# TDC.net
KiCad netlist of a schematic drawn in Altium Designer
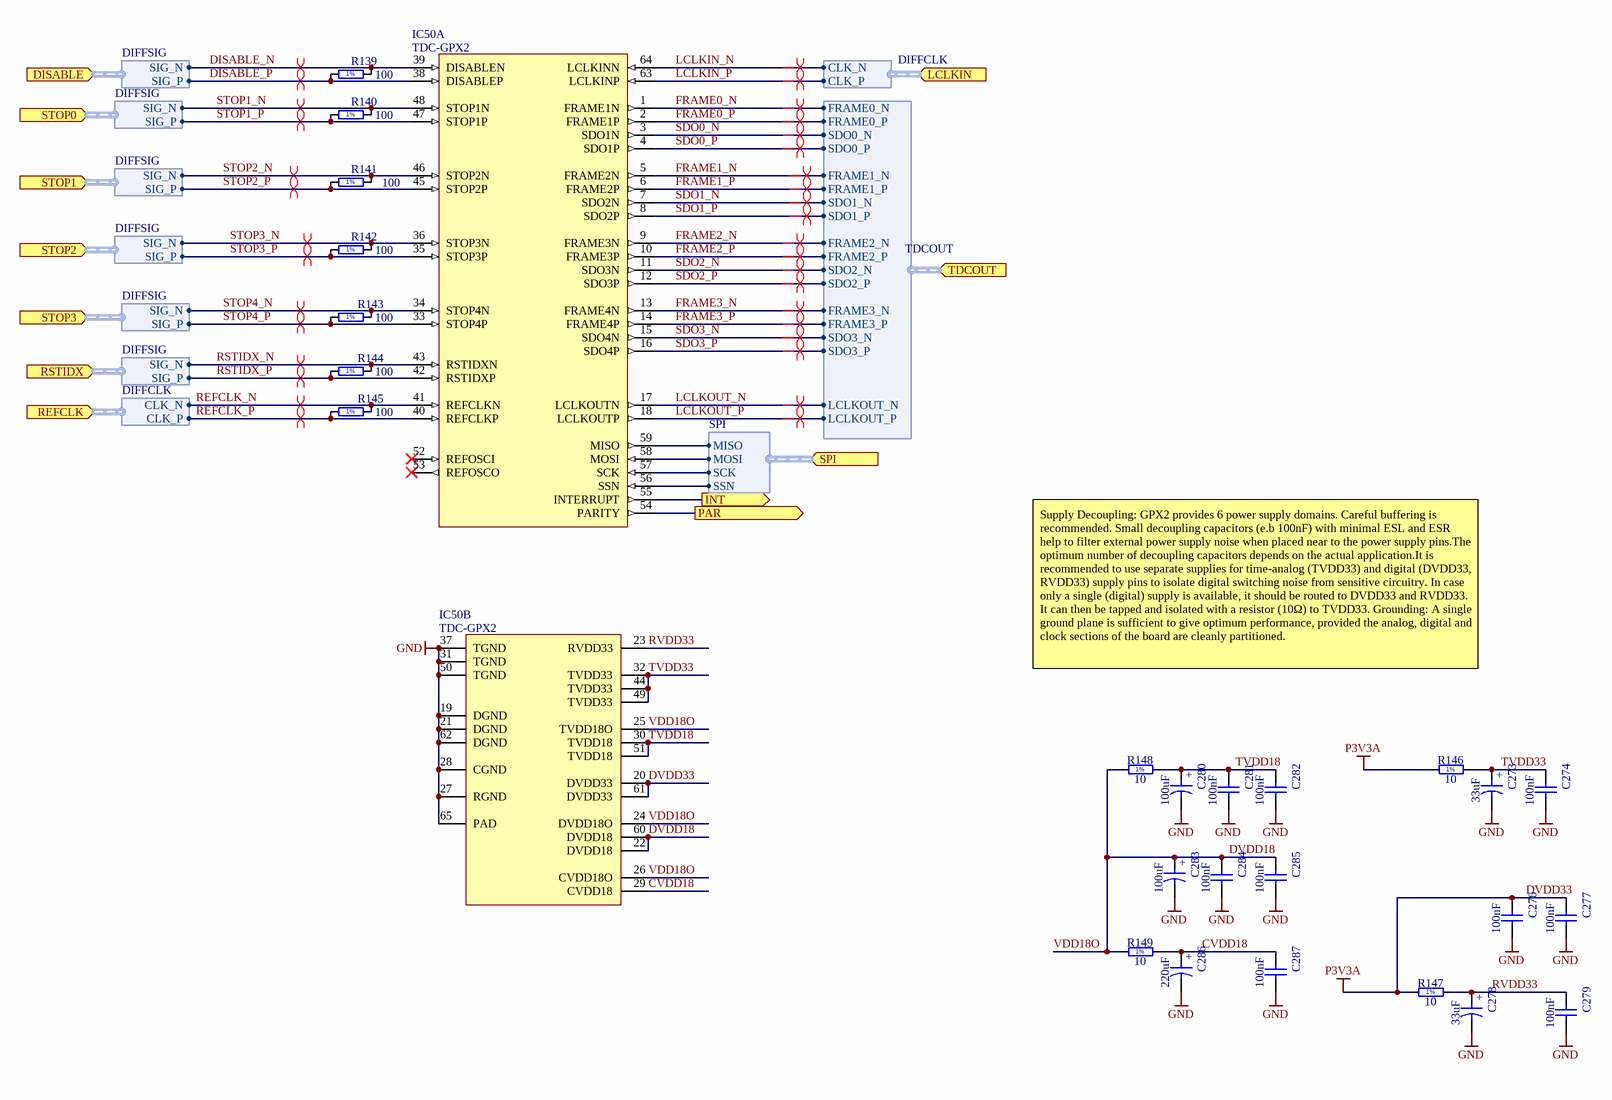
[diagram p0: TDC.SchDoc]

(export (version "E")
  (design (tool "Eeschema 10.0.6"))
  (components
    (comp (ref "C273")
      (value "33uF")
      (footprint "CAPMP3216X180N")
      (description "Polarised capacitor")
      (fields
        (field (name "PART NUMBER") "CTE3216-18_33UF_4V_10%")
        (field (name "VOLTAGE") "4V")
        (field (name "AUTHOR") "CERN DEM JLC")
      )
      (libsource (lib "Capacitors") (part "Capacitor - polarized"))
    )
    (comp (ref "C274")
      (value "100nF")
      (footprint "CAPC0603X33N")
      (description "Non-polarised capacitor")
      (fields
        (field (name "PART NUMBER") "CC0201_100NF_6.3V_10%_X5R")
        (field (name "VOLTAGE") "6.3V")
        (field (name "AUTHOR") "CERN DEM JLC")
      )
      (libsource (lib "Capacitors") (part "Capacitor - non polarized"))
    )
    (comp (ref "C276")
      (value "100nF")
      (footprint "CAPC0603X33N")
      (description "Non-polarised capacitor")
      (fields
        (field (name "PART NUMBER") "CC0201_100NF_6.3V_10%_X5R")
        (field (name "VOLTAGE") "6.3V")
        (field (name "AUTHOR") "CERN DEM JLC")
      )
      (libsource (lib "Capacitors") (part "Capacitor - non polarized"))
    )
    (comp (ref "C277")
      (value "100nF")
      (footprint "CAPC0603X33N")
      (description "Non-polarised capacitor")
      (fields
        (field (name "PART NUMBER") "CC0201_100NF_6.3V_10%_X5R")
        (field (name "VOLTAGE") "6.3V")
        (field (name "AUTHOR") "CERN DEM JLC")
      )
      (libsource (lib "Capacitors") (part "Capacitor - non polarized"))
    )
    (comp (ref "C278")
      (value "33uF")
      (footprint "CAPMP3216X180N")
      (description "Polarised capacitor")
      (fields
        (field (name "PART NUMBER") "CTE3216-18_33UF_4V_10%")
        (field (name "VOLTAGE") "4V")
        (field (name "AUTHOR") "CERN DEM JLC")
      )
      (libsource (lib "Capacitors") (part "Capacitor - polarized"))
    )
    (comp (ref "C279")
      (value "100nF")
      (footprint "CAPC0603X33N")
      (description "Non-polarised capacitor")
      (fields
        (field (name "PART NUMBER") "CC0201_100NF_6.3V_10%_X5R")
        (field (name "VOLTAGE") "6.3V")
        (field (name "AUTHOR") "CERN DEM JLC")
      )
      (libsource (lib "Capacitors") (part "Capacitor - non polarized"))
    )
    (comp (ref "C280")
      (value "100uF")
      (footprint "CAPMP3216X180N")
      (description "Polarised capacitor")
      (fields
        (field (name "PART NUMBER") "CTE3216-18_100UF_6.3V_20%_ESR0500_AVX_TLJ")
        (field (name "VOLTAGE") "6.3V")
        (field (name "AUTHOR") "CERN DEM JLC")
      )
      (libsource (lib "Capacitors") (part "Capacitor - polarized"))
    )
    (comp (ref "C281")
      (value "100nF")
      (footprint "CAPC0603X33N")
      (description "Non-polarised capacitor")
      (fields
        (field (name "PART NUMBER") "CC0201_100NF_6.3V_10%_X5R")
        (field (name "VOLTAGE") "6.3V")
        (field (name "AUTHOR") "CERN DEM JLC")
      )
      (libsource (lib "Capacitors") (part "Capacitor - non polarized"))
    )
    (comp (ref "C282")
      (value "100nF")
      (footprint "CAPC0603X33N")
      (description "Non-polarised capacitor")
      (fields
        (field (name "PART NUMBER") "CC0201_100NF_6.3V_10%_X5R")
        (field (name "VOLTAGE") "6.3V")
        (field (name "AUTHOR") "CERN DEM JLC")
      )
      (libsource (lib "Capacitors") (part "Capacitor - non polarized"))
    )
    (comp (ref "C283")
      (value "100uF")
      (footprint "CAPMP3216X180N")
      (description "Polarised capacitor")
      (fields
        (field (name "PART NUMBER") "CTE3216-18_100UF_6.3V_20%_ESR0500_AVX_TLJ")
        (field (name "VOLTAGE") "6.3V")
        (field (name "AUTHOR") "CERN DEM JLC")
      )
      (libsource (lib "Capacitors") (part "Capacitor - polarized"))
    )
    (comp (ref "C284")
      (value "100nF")
      (footprint "CAPC0603X33N")
      (description "Non-polarised capacitor")
      (fields
        (field (name "PART NUMBER") "CC0201_100NF_6.3V_10%_X5R")
        (field (name "VOLTAGE") "6.3V")
        (field (name "AUTHOR") "CERN DEM JLC")
      )
      (libsource (lib "Capacitors") (part "Capacitor - non polarized"))
    )
    (comp (ref "C285")
      (value "100nF")
      (footprint "CAPC0603X33N")
      (description "Non-polarised capacitor")
      (fields
        (field (name "PART NUMBER") "CC0201_100NF_6.3V_10%_X5R")
        (field (name "VOLTAGE") "6.3V")
        (field (name "AUTHOR") "CERN DEM JLC")
      )
      (libsource (lib "Capacitors") (part "Capacitor - non polarized"))
    )
    (comp (ref "C286")
      (value "220uF")
      (footprint "CAPMP3528X210N")
      (description "Polarised capacitor")
      (fields
        (field (name "PART NUMBER") "CTE3528-21_220UF_2.5V_10%")
        (field (name "VOLTAGE") "2.5V")
        (field (name "AUTHOR") "CERN DEM JLC")
      )
      (libsource (lib "Capacitors") (part "Capacitor - polarized"))
    )
    (comp (ref "C287")
      (value "100nF")
      (footprint "CAPC0603X33N")
      (description "Non-polarised capacitor")
      (fields
        (field (name "PART NUMBER") "CC0201_100NF_6.3V_10%_X5R")
        (field (name "VOLTAGE") "6.3V")
        (field (name "AUTHOR") "CERN DEM JLC")
      )
      (libsource (lib "Capacitors") (part "Capacitor - non polarized"))
    )
    (comp (ref "IC50")
      (value "TDC-GPX2")
      (footprint "QFN50P900X900X100-65N-S615")
      (description "4-Channel Time-to-Digital Converter")
      (fields (field (name "MANUFACTURER") "ACAM MESS-ELECTRONIC") (field (name "AUTHOR") "GK"))
      (libsource (lib "ICs_Analog_Interfaces") (part "TDC-GPX2"))
    )
    (comp (ref "R139")
      (value "100")
      (footprint "RESC0603X28N")
      (description "Resistor - 1%")
      (fields
        (field (name "PART NUMBER") "R0201_100R_1%_0.05W_200PPM")
        (field (name "POWER") "0.05W")
        (field (name "AUTHOR") "CERN DEM JLC")
      )
      (libsource (lib "Resistors") (part "Resistor - 1%"))
    )
    (comp (ref "R140")
      (value "100")
      (footprint "RESC0603X28N")
      (description "Resistor - 1%")
      (fields
        (field (name "PART NUMBER") "R0201_100R_1%_0.05W_200PPM")
        (field (name "POWER") "0.05W")
        (field (name "AUTHOR") "CERN DEM JLC")
      )
      (libsource (lib "Resistors") (part "Resistor - 1%"))
    )
    (comp (ref "R141")
      (value "100")
      (footprint "RESC0603X28N")
      (description "Resistor - 1%")
      (fields
        (field (name "PART NUMBER") "R0201_100R_1%_0.05W_200PPM")
        (field (name "POWER") "0.05W")
        (field (name "AUTHOR") "CERN DEM JLC")
      )
      (libsource (lib "Resistors") (part "Resistor - 1%"))
    )
    (comp (ref "R142")
      (value "100")
      (footprint "RESC0603X28N")
      (description "Resistor - 1%")
      (fields
        (field (name "PART NUMBER") "R0201_100R_1%_0.05W_200PPM")
        (field (name "POWER") "0.05W")
        (field (name "AUTHOR") "CERN DEM JLC")
      )
      (libsource (lib "Resistors") (part "Resistor - 1%"))
    )
    (comp (ref "R143")
      (value "100")
      (footprint "RESC0603X28N")
      (description "Resistor - 1%")
      (fields
        (field (name "PART NUMBER") "R0201_100R_1%_0.05W_200PPM")
        (field (name "POWER") "0.05W")
        (field (name "AUTHOR") "CERN DEM JLC")
      )
      (libsource (lib "Resistors") (part "Resistor - 1%"))
    )
    (comp (ref "R144")
      (value "100")
      (footprint "RESC0603X28N")
      (description "Resistor - 1%")
      (fields
        (field (name "PART NUMBER") "R0201_100R_1%_0.05W_200PPM")
        (field (name "POWER") "0.05W")
        (field (name "AUTHOR") "CERN DEM JLC")
      )
      (libsource (lib "Resistors") (part "Resistor - 1%"))
    )
    (comp (ref "R145")
      (value "100")
      (footprint "RESC0603X28N")
      (description "Resistor - 1%")
      (fields
        (field (name "PART NUMBER") "R0201_100R_1%_0.05W_200PPM")
        (field (name "POWER") "0.05W")
        (field (name "AUTHOR") "CERN DEM JLC")
      )
      (libsource (lib "Resistors") (part "Resistor - 1%"))
    )
    (comp (ref "R146")
      (value "10")
      (footprint "RESC1005X40N")
      (description "Resistor - 1%")
      (fields
        (field (name "PART NUMBER") "R0402_10R_1%_0.0625W_200PPM")
        (field (name "POWER") "0.0625W")
        (field (name "AUTHOR") "CERN DEM JLC")
      )
      (libsource (lib "Resistors") (part "Resistor - 1%"))
    )
    (comp (ref "R147")
      (value "10")
      (footprint "RESC1005X40N")
      (description "Resistor - 1%")
      (fields
        (field (name "PART NUMBER") "R0402_10R_1%_0.0625W_200PPM")
        (field (name "POWER") "0.0625W")
        (field (name "AUTHOR") "CERN DEM JLC")
      )
      (libsource (lib "Resistors") (part "Resistor - 1%"))
    )
    (comp (ref "R148")
      (value "10")
      (footprint "RESC1005X40N")
      (description "Resistor - 1%")
      (fields
        (field (name "PART NUMBER") "R0402_10R_1%_0.0625W_200PPM")
        (field (name "POWER") "0.0625W")
        (field (name "AUTHOR") "CERN DEM JLC")
      )
      (libsource (lib "Resistors") (part "Resistor - 1%"))
    )
    (comp (ref "R149")
      (value "10")
      (footprint "RESC1005X40N")
      (description "Resistor - 1%")
      (fields
        (field (name "PART NUMBER") "R0402_10R_1%_0.0625W_200PPM")
        (field (name "POWER") "0.0625W")
        (field (name "AUTHOR") "CERN DEM JLC")
      )
      (libsource (lib "Resistors") (part "Resistor - 1%"))
    )
  )
  (nets
    (net (code "5") (name "/CVDD18") (class "Default")
      (node (ref "C286") (pin "1") (pinfunction "1_1") (pintype "passive"))
      (node (ref "C287") (pin "1") (pinfunction "1_1") (pintype "passive"))
      (node (ref "IC50") (pin "29") (pinfunction "CVDD18_29") (pintype "power_in"))
      (node (ref "R149") (pin "2") (pinfunction "2_2") (pintype "passive"))
    )
    (net (code "6") (name "/DISABLE_N") (class "Default")
      (node (ref "IC50") (pin "39") (pinfunction "DISABLEN_39") (pintype "input"))
      (node (ref "R139") (pin "2") (pinfunction "2_2") (pintype "passive"))
    )
    (net (code "7") (name "/DISABLE_P") (class "Default")
      (node (ref "IC50") (pin "38") (pinfunction "DISABLEP_38") (pintype "input"))
      (node (ref "R139") (pin "1") (pinfunction "1_1") (pintype "passive"))
    )
    (net (code "8") (name "/DVDD18") (class "Default")
      (node (ref "C283") (pin "1") (pinfunction "1_1") (pintype "passive"))
      (node (ref "C284") (pin "1") (pinfunction "1_1") (pintype "passive"))
      (node (ref "C285") (pin "1") (pinfunction "1_1") (pintype "passive"))
      (node (ref "IC50") (pin "22") (pinfunction "DVDD18_22") (pintype "power_in"))
      (node (ref "IC50") (pin "24") (pinfunction "DVDD18O_24") (pintype "power_in"))
      (node (ref "IC50") (pin "25") (pinfunction "TVDD18O_25") (pintype "power_in"))
      (node (ref "IC50") (pin "26") (pinfunction "CVDD18O_26") (pintype "power_in"))
      (node (ref "IC50") (pin "60") (pinfunction "DVDD18_60") (pintype "power_in"))
      (node (ref "R148") (pin "1") (pinfunction "1_1") (pintype "passive"))
      (node (ref "R149") (pin "1") (pinfunction "1_1") (pintype "passive"))
    )
    (net (code "9") (name "/FRAME0_N") (class "Default")
      (node (ref "IC50") (pin "1") (pinfunction "FRAME1N_1") (pintype "output"))
    )
    (net (code "10") (name "/FRAME0_P") (class "Default")
      (node (ref "IC50") (pin "2") (pinfunction "FRAME1P_2") (pintype "output"))
    )
    (net (code "11") (name "/FRAME1_N") (class "Default")
      (node (ref "IC50") (pin "5") (pinfunction "FRAME2N_5") (pintype "output"))
    )
    (net (code "12") (name "/FRAME1_P") (class "Default")
      (node (ref "IC50") (pin "6") (pinfunction "FRAME2P_6") (pintype "output"))
    )
    (net (code "13") (name "/FRAME2_N") (class "Default")
      (node (ref "IC50") (pin "9") (pinfunction "FRAME3N_9") (pintype "output"))
    )
    (net (code "14") (name "/FRAME2_P") (class "Default")
      (node (ref "IC50") (pin "10") (pinfunction "FRAME3P_10") (pintype "output"))
    )
    (net (code "15") (name "/FRAME3_N") (class "Default")
      (node (ref "IC50") (pin "13") (pinfunction "FRAME4N_13") (pintype "output"))
    )
    (net (code "16") (name "/FRAME3_P") (class "Default")
      (node (ref "IC50") (pin "14") (pinfunction "FRAME4P_14") (pintype "output"))
    )
    (net (code "17") (name "/INT") (class "Default")
      (node (ref "IC50") (pin "55") (pinfunction "INTERRUPT_55") (pintype "output"))
    )
    (net (code "18") (name "/LCLKIN_N") (class "Default")
      (node (ref "IC50") (pin "64") (pinfunction "LCLKINN_64") (pintype "input"))
    )
    (net (code "19") (name "/LCLKIN_P") (class "Default")
      (node (ref "IC50") (pin "63") (pinfunction "LCLKINP_63") (pintype "input"))
    )
    (net (code "20") (name "/LCLKOUT_N") (class "Default")
      (node (ref "IC50") (pin "17") (pinfunction "LCLKOUTN_17") (pintype "output"))
    )
    (net (code "21") (name "/LCLKOUT_P") (class "Default")
      (node (ref "IC50") (pin "18") (pinfunction "LCLKOUTP_18") (pintype "output"))
    )
    (net (code "22") (name "/MISO") (class "Default")
      (node (ref "IC50") (pin "59") (pinfunction "MISO_59") (pintype "output"))
    )
    (net (code "23") (name "/MOSI") (class "Default")
      (node (ref "IC50") (pin "58") (pinfunction "MOSI_58") (pintype "input"))
    )
    (net (code "24") (name "/PAR") (class "Default")
      (node (ref "IC50") (pin "54") (pinfunction "PARITY_54") (pintype "output"))
    )
    (net (code "25") (name "/REFCLK_N") (class "Default")
      (node (ref "IC50") (pin "41") (pinfunction "REFCLKN_41") (pintype "input"))
      (node (ref "R145") (pin "2") (pinfunction "2_2") (pintype "passive"))
    )
    (net (code "26") (name "/REFCLK_P") (class "Default")
      (node (ref "IC50") (pin "40") (pinfunction "REFCLKP_40") (pintype "input"))
      (node (ref "R145") (pin "1") (pinfunction "1_1") (pintype "passive"))
    )
    (net (code "27") (name "/RSTIDX_N") (class "Default")
      (node (ref "IC50") (pin "43") (pinfunction "RSTIDXN_43") (pintype "input"))
      (node (ref "R144") (pin "2") (pinfunction "2_2") (pintype "passive"))
    )
    (net (code "28") (name "/RSTIDX_P") (class "Default")
      (node (ref "IC50") (pin "42") (pinfunction "RSTIDXP_42") (pintype "input"))
      (node (ref "R144") (pin "1") (pinfunction "1_1") (pintype "passive"))
    )
    (net (code "29") (name "/RVDD33") (class "Default")
      (node (ref "C278") (pin "1") (pinfunction "1_1") (pintype "passive"))
      (node (ref "C279") (pin "1") (pinfunction "1_1") (pintype "passive"))
      (node (ref "IC50") (pin "23") (pinfunction "RVDD33_23") (pintype "power_in"))
      (node (ref "R147") (pin "2") (pinfunction "2_2") (pintype "passive"))
    )
    (net (code "30") (name "/SCK") (class "Default")
      (node (ref "IC50") (pin "57") (pinfunction "SCK_57") (pintype "input"))
    )
    (net (code "31") (name "/SDO0_N") (class "Default")
      (node (ref "IC50") (pin "3") (pinfunction "SDO1N_3") (pintype "output"))
    )
    (net (code "32") (name "/SDO0_P") (class "Default")
      (node (ref "IC50") (pin "4") (pinfunction "SDO1P_4") (pintype "output"))
    )
    (net (code "33") (name "/SDO1_N") (class "Default")
      (node (ref "IC50") (pin "7") (pinfunction "SDO2N_7") (pintype "output"))
    )
    (net (code "34") (name "/SDO1_P") (class "Default")
      (node (ref "IC50") (pin "8") (pinfunction "SDO2P_8") (pintype "output"))
    )
    (net (code "35") (name "/SDO2_N") (class "Default")
      (node (ref "IC50") (pin "11") (pinfunction "SDO3N_11") (pintype "output"))
    )
    (net (code "36") (name "/SDO2_P") (class "Default")
      (node (ref "IC50") (pin "12") (pinfunction "SDO3P_12") (pintype "output"))
    )
    (net (code "37") (name "/SDO3_N") (class "Default")
      (node (ref "IC50") (pin "15") (pinfunction "SDO4N_15") (pintype "output"))
    )
    (net (code "38") (name "/SDO3_P") (class "Default")
      (node (ref "IC50") (pin "16") (pinfunction "SDO4P_16") (pintype "output"))
    )
    (net (code "39") (name "/SSN") (class "Default")
      (node (ref "IC50") (pin "56") (pinfunction "SSN_56") (pintype "input"))
    )
    (net (code "40") (name "/STOP1_N") (class "Default")
      (node (ref "IC50") (pin "48") (pinfunction "STOP1N_48") (pintype "input"))
      (node (ref "R140") (pin "2") (pinfunction "2_2") (pintype "passive"))
    )
    (net (code "41") (name "/STOP1_P") (class "Default")
      (node (ref "IC50") (pin "47") (pinfunction "STOP1P_47") (pintype "input"))
      (node (ref "R140") (pin "1") (pinfunction "1_1") (pintype "passive"))
    )
    (net (code "42") (name "/STOP2_N") (class "Default")
      (node (ref "IC50") (pin "46") (pinfunction "STOP2N_46") (pintype "input"))
      (node (ref "R141") (pin "2") (pinfunction "2_2") (pintype "passive"))
    )
    (net (code "43") (name "/STOP2_P") (class "Default")
      (node (ref "IC50") (pin "45") (pinfunction "STOP2P_45") (pintype "input"))
      (node (ref "R141") (pin "1") (pinfunction "1_1") (pintype "passive"))
    )
    (net (code "44") (name "/STOP3_N") (class "Default")
      (node (ref "IC50") (pin "36") (pinfunction "STOP3N_36") (pintype "input"))
      (node (ref "R142") (pin "2") (pinfunction "2_2") (pintype "passive"))
    )
    (net (code "45") (name "/STOP3_P") (class "Default")
      (node (ref "IC50") (pin "35") (pinfunction "STOP3P_35") (pintype "input"))
      (node (ref "R142") (pin "1") (pinfunction "1_1") (pintype "passive"))
    )
    (net (code "46") (name "/STOP4_N") (class "Default")
      (node (ref "IC50") (pin "34") (pinfunction "STOP4N_34") (pintype "input"))
      (node (ref "R143") (pin "2") (pinfunction "2_2") (pintype "passive"))
    )
    (net (code "47") (name "/STOP4_P") (class "Default")
      (node (ref "IC50") (pin "33") (pinfunction "STOP4P_33") (pintype "input"))
      (node (ref "R143") (pin "1") (pinfunction "1_1") (pintype "passive"))
    )
    (net (code "48") (name "/TVDD18") (class "Default")
      (node (ref "C280") (pin "1") (pinfunction "1_1") (pintype "passive"))
      (node (ref "C281") (pin "1") (pinfunction "1_1") (pintype "passive"))
      (node (ref "C282") (pin "1") (pinfunction "1_1") (pintype "passive"))
      (node (ref "IC50") (pin "30") (pinfunction "TVDD18_30") (pintype "power_in"))
      (node (ref "IC50") (pin "51") (pinfunction "TVDD18_51") (pintype "power_in"))
      (node (ref "R148") (pin "2") (pinfunction "2_2") (pintype "passive"))
    )
    (net (code "49") (name "/TVDD33") (class "Default")
      (node (ref "C273") (pin "1") (pinfunction "1_1") (pintype "passive"))
      (node (ref "C274") (pin "1") (pinfunction "1_1") (pintype "passive"))
      (node (ref "IC50") (pin "32") (pinfunction "TVDD33_32") (pintype "power_in"))
      (node (ref "IC50") (pin "44") (pinfunction "TVDD33_44") (pintype "power_in"))
      (node (ref "IC50") (pin "49") (pinfunction "TVDD33_49") (pintype "power_in"))
      (node (ref "R146") (pin "2") (pinfunction "2_2") (pintype "passive"))
    )
    (net (code "54") (name "GND") (class "Default")
      (node (ref "C273") (pin "2") (pinfunction "2_2") (pintype "passive"))
      (node (ref "C274") (pin "2") (pinfunction "2_2") (pintype "passive"))
      (node (ref "C276") (pin "2") (pinfunction "2_2") (pintype "passive"))
      (node (ref "C277") (pin "2") (pinfunction "2_2") (pintype "passive"))
      (node (ref "C278") (pin "2") (pinfunction "2_2") (pintype "passive"))
      (node (ref "C279") (pin "2") (pinfunction "2_2") (pintype "passive"))
      (node (ref "C280") (pin "2") (pinfunction "2_2") (pintype "passive"))
      (node (ref "C281") (pin "2") (pinfunction "2_2") (pintype "passive"))
      (node (ref "C282") (pin "2") (pinfunction "2_2") (pintype "passive"))
      (node (ref "C283") (pin "2") (pinfunction "2_2") (pintype "passive"))
      (node (ref "C284") (pin "2") (pinfunction "2_2") (pintype "passive"))
      (node (ref "C285") (pin "2") (pinfunction "2_2") (pintype "passive"))
      (node (ref "C286") (pin "2") (pinfunction "2_2") (pintype "passive"))
      (node (ref "C287") (pin "2") (pinfunction "2_2") (pintype "passive"))
      (node (ref "IC50") (pin "19") (pinfunction "DGND_19") (pintype "power_in"))
      (node (ref "IC50") (pin "21") (pinfunction "DGND_21") (pintype "power_in"))
      (node (ref "IC50") (pin "27") (pinfunction "RGND_27") (pintype "power_in"))
      (node (ref "IC50") (pin "28") (pinfunction "CGND_28") (pintype "power_in"))
      (node (ref "IC50") (pin "31") (pinfunction "TGND_31") (pintype "power_in"))
      (node (ref "IC50") (pin "37") (pinfunction "TGND_37") (pintype "power_in"))
      (node (ref "IC50") (pin "50") (pinfunction "TGND_50") (pintype "power_in"))
      (node (ref "IC50") (pin "62") (pinfunction "DGND_62") (pintype "power_in"))
      (node (ref "IC50") (pin "65") (pinfunction "PAD_65") (pintype "power_in"))
    )
    (net (code "55") (name "P3V3A") (class "Default")
      (node (ref "C276") (pin "1") (pinfunction "1_1") (pintype "passive"))
      (node (ref "C277") (pin "1") (pinfunction "1_1") (pintype "passive"))
      (node (ref "IC50") (pin "20") (pinfunction "DVDD33_20") (pintype "power_in"))
      (node (ref "IC50") (pin "61") (pinfunction "DVDD33_61") (pintype "power_in"))
      (node (ref "R146") (pin "1") (pinfunction "1_1") (pintype "passive"))
      (node (ref "R147") (pin "1") (pinfunction "1_1") (pintype "passive"))
    )
    (net (code "56") (name "unconnected-(IC50A-REFOSCI-Pad52)") (class "Default")
      (node (ref "IC50") (pin "52") (pinfunction "REFOSCI_52") (pintype "input+no_connect"))
    )
    (net (code "57") (name "unconnected-(IC50A-REFOSCO-Pad53)") (class "Default")
      (node (ref "IC50") (pin "53") (pinfunction "REFOSCO_53") (pintype "output+no_connect"))
    )
  )
)
